# ASM001-design-1.net
KiCad netlist of a schematic drawn in Altium Designer
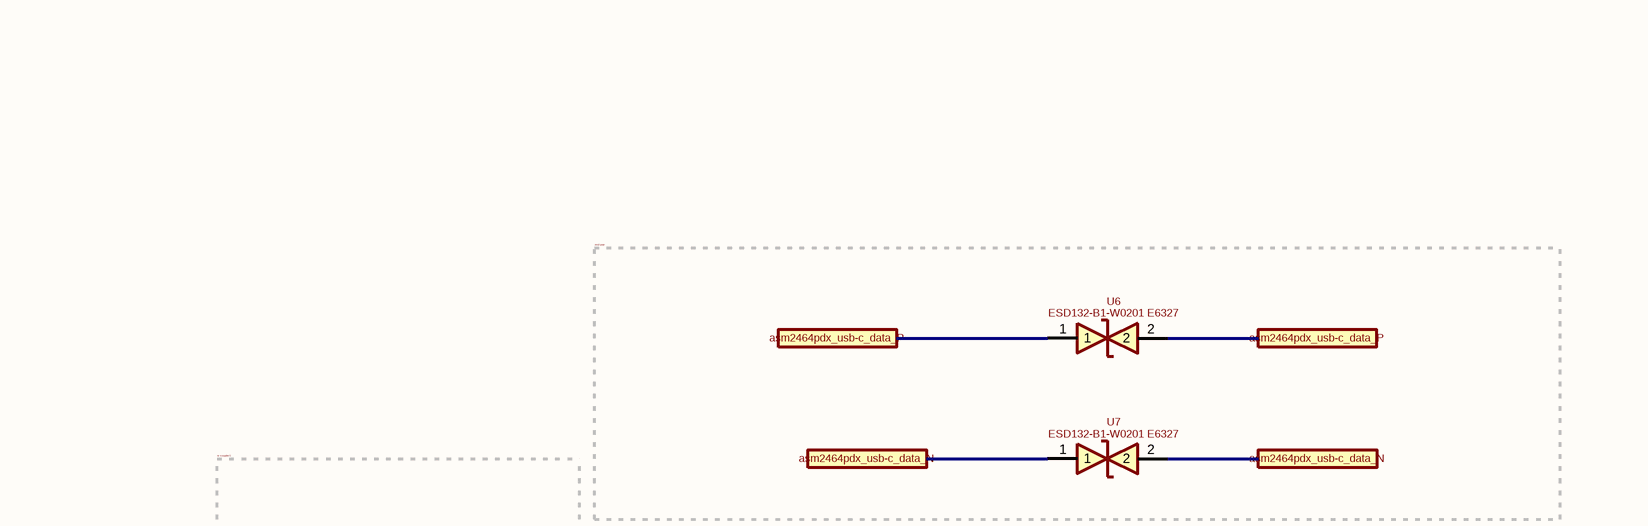
[diagram p0: ASM001-design-1.SchDoc, top column 2 of 4]
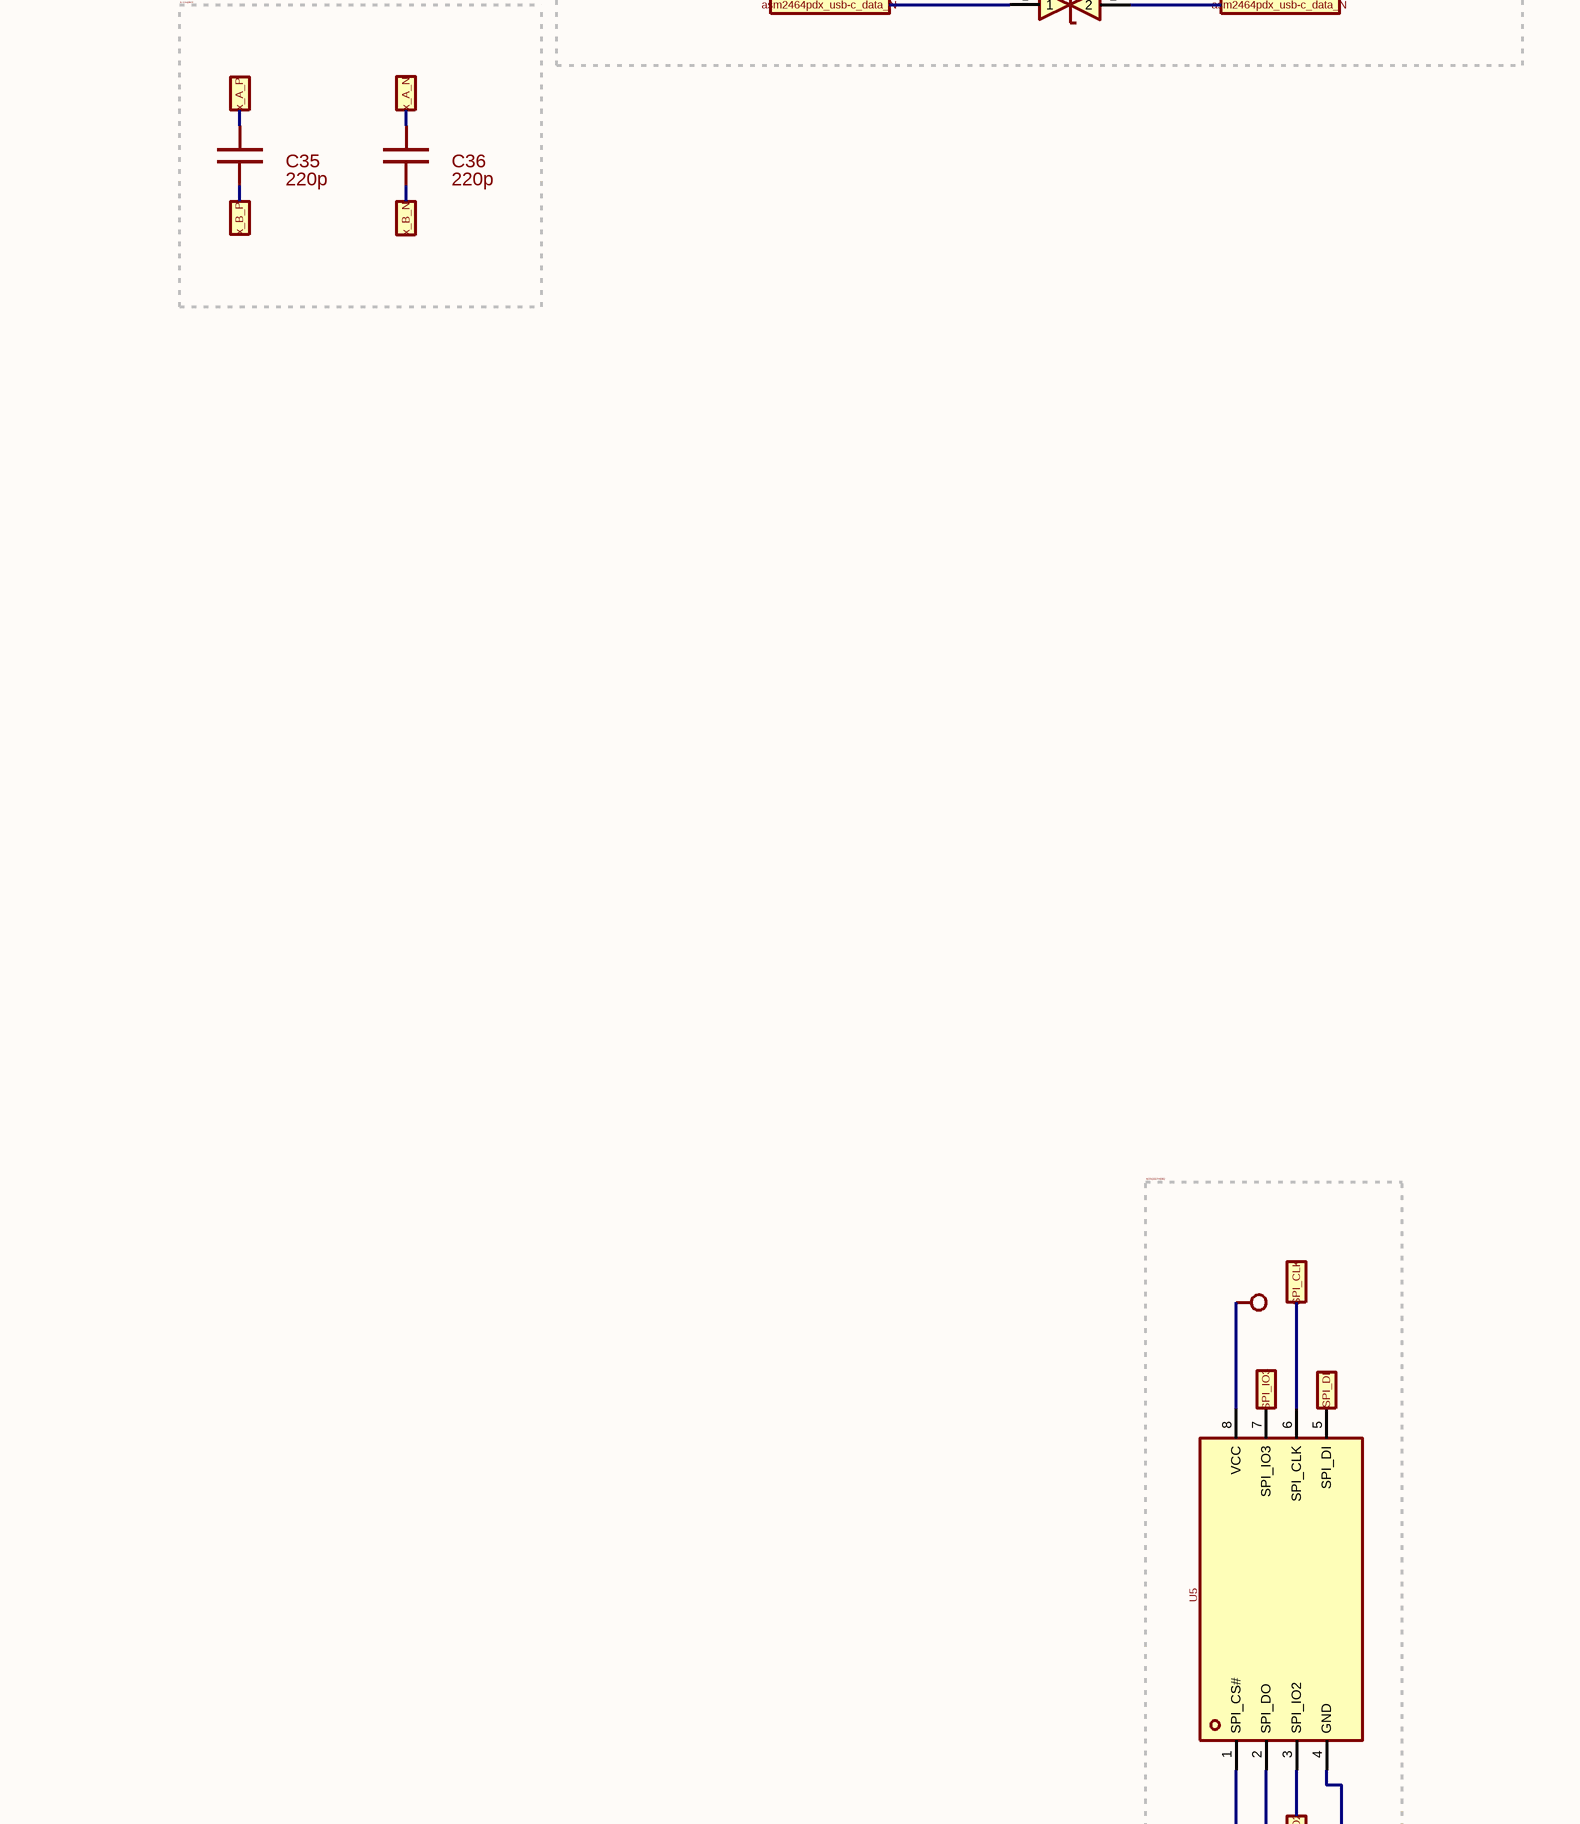
[diagram p1: ASM001-design-1.SchDoc, centre column 2 of 4]
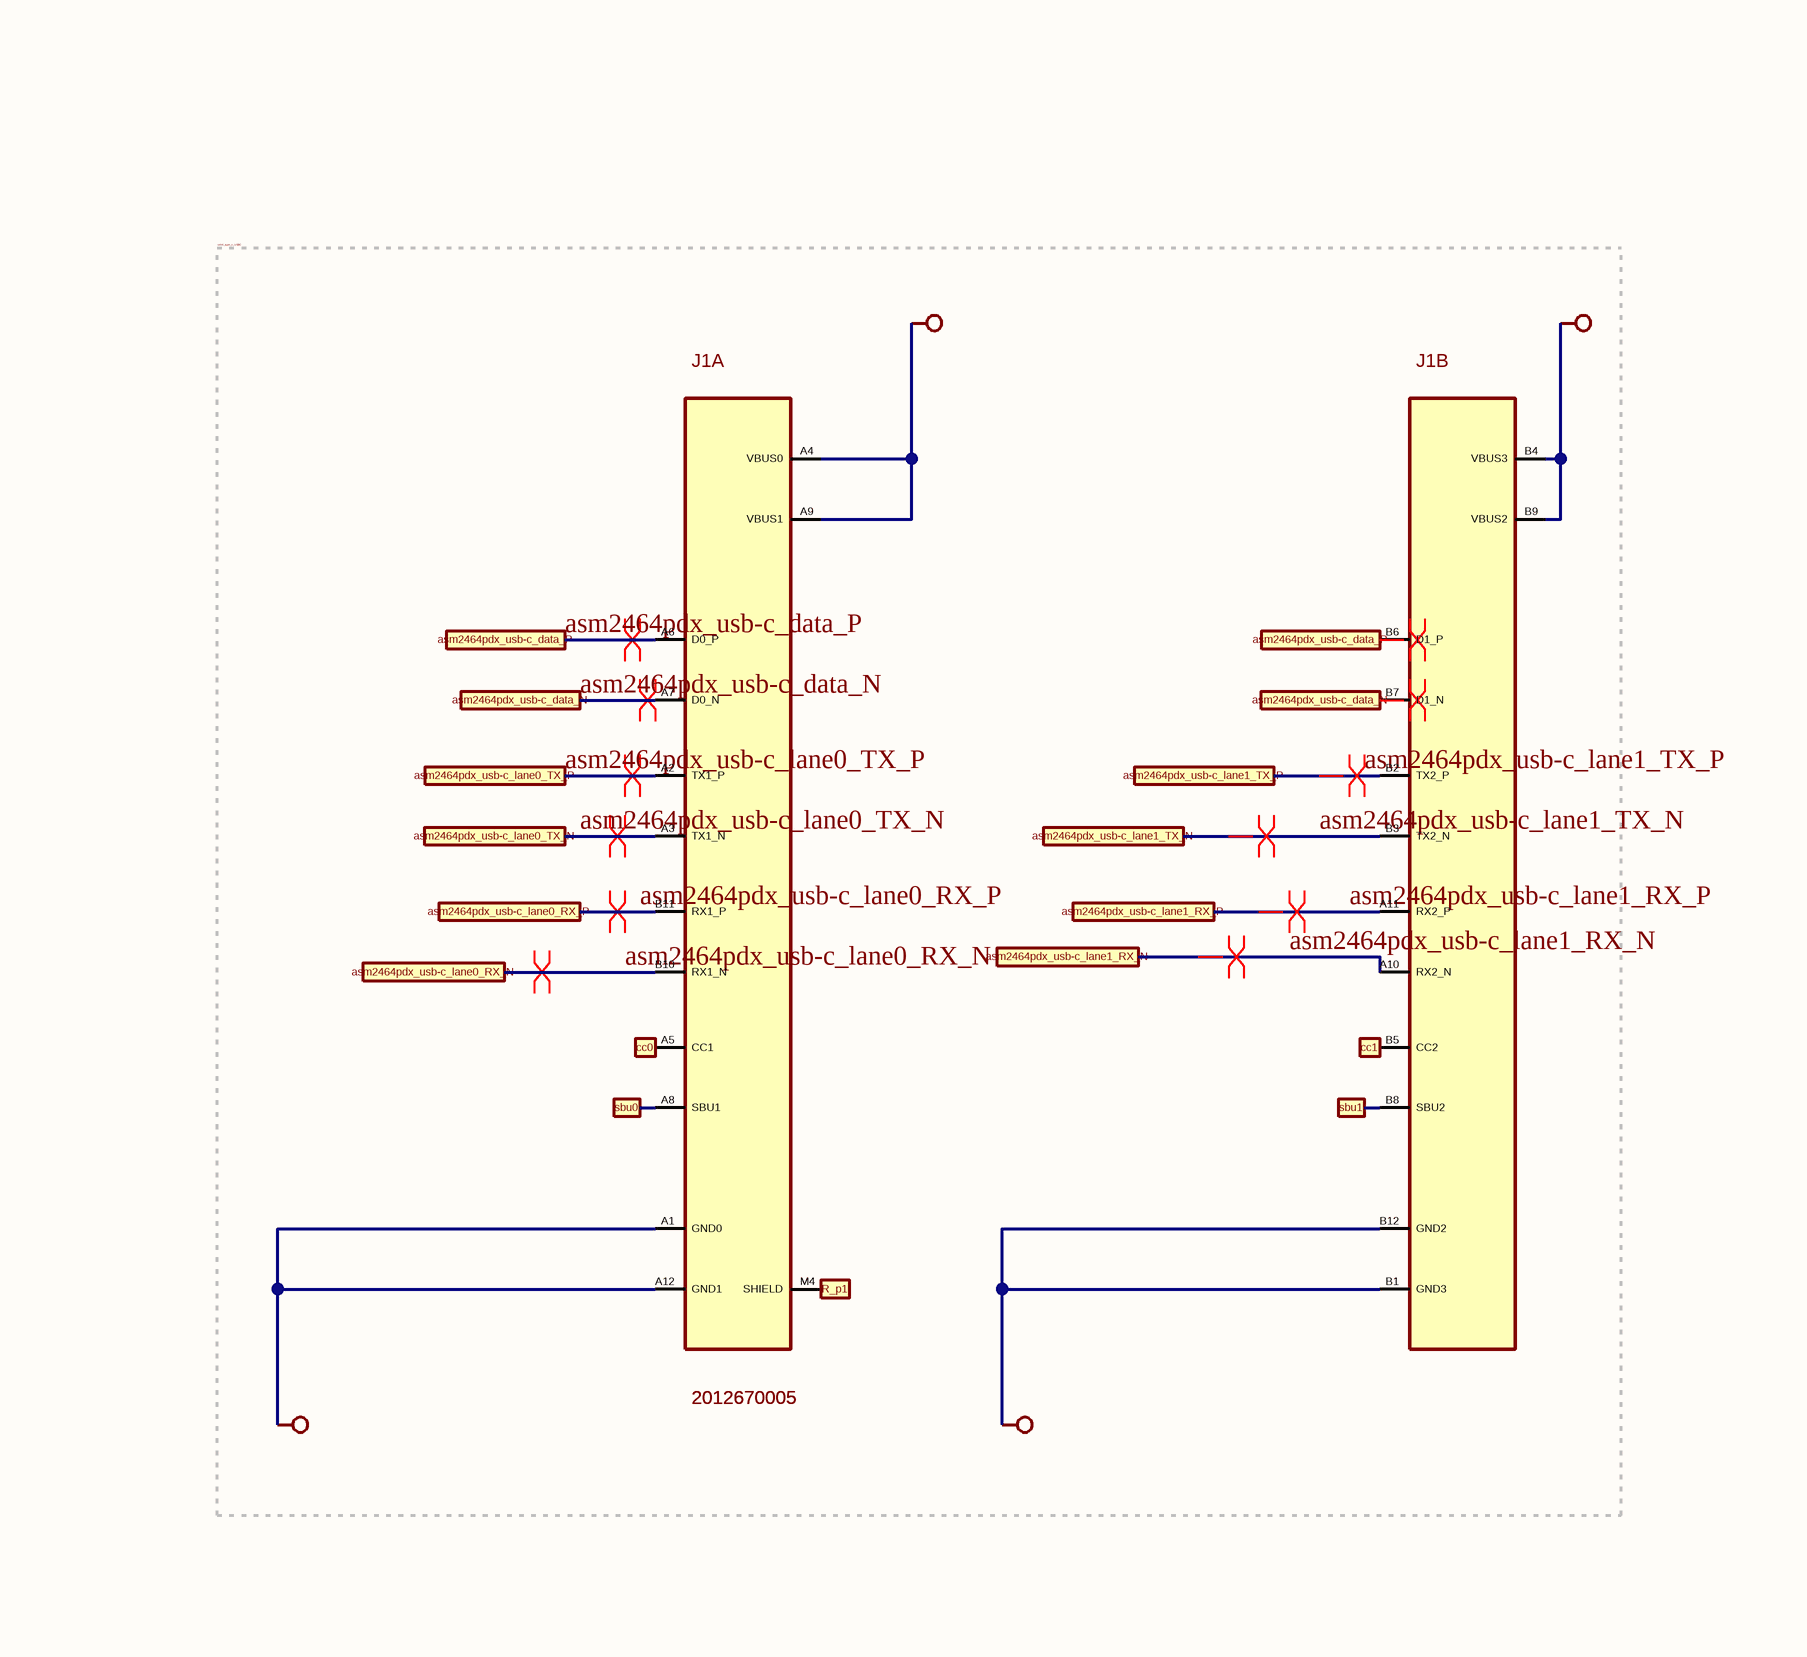
[diagram p2: ASM001-design-1.SchDoc, centre column 3 of 4]
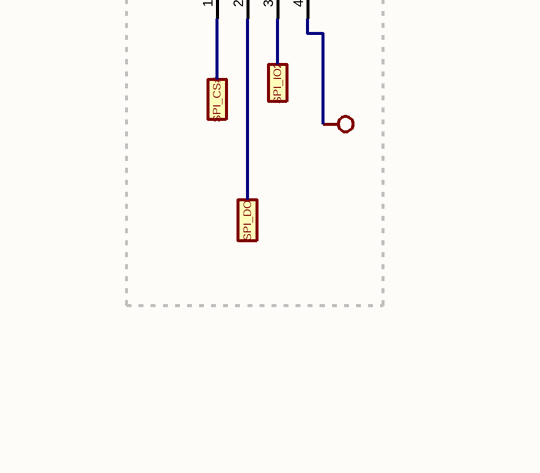
[diagram p3: ASM001-design-1.SchDoc, bottom column 2 of 4]
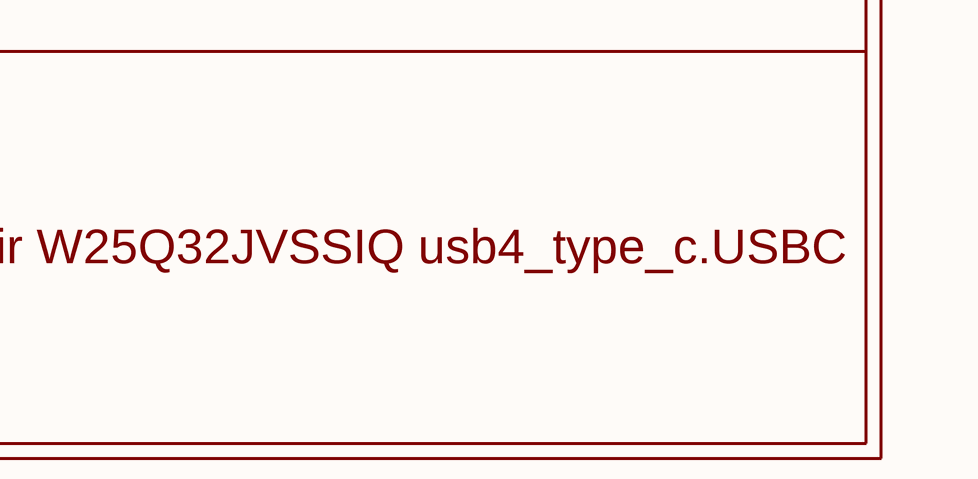
[diagram p4: ASM001-design-1.SchDoc, bottom column 4 of 4]

(export (version "E")
  (design (tool "Eeschema 10.0.6"))
  (components
    (comp (ref "C35")
      (value "220p")
      (footprint "SMT_0201$1")
      (description "block_cap")
      (fields (field (name "TOLERANCE") "0.2%") (field (name "MPN") "02013A1R5BAT2A"))
      (libsource (lib "ASM001-design") (part "block_cap"))
    )
    (comp (ref "C36")
      (value "220p")
      (footprint "SMT_0201$1")
      (description "block_cap")
      (fields (field (name "TOLERANCE") "0.2%") (field (name "MPN") "02013A1R5BAT2A"))
      (libsource (lib "ASM001-design") (part "block_cap"))
    )
    (comp (ref "J1")
      (value "2012670005")
      (footprint "USB_TYPE_C_CONNECTOR")
      (description "conn_component")
      (fields (field (name "ALTIUM_VALUE") "2012670005") (field (name "MANUFACTURER") "Molex"))
      (libsource (lib "ASM001-design") (part "conn_component"))
    )
    (comp (ref "U5")
      (value "W25Q32JVSSIQ")
      (footprint "LP$1")
      (description "C82344")
      (fields (field (name "MANUFACTURER") "Winbond"))
      (libsource (lib "ASM001-design") (part "C82344"))
    )
    (comp (ref "U6")
      (value "ESD132-B1-W0201 E6327")
      (footprint "LP$3")
      (description "C535164")
      (fields (field (name "MANUFACTURER") "Infineon"))
      (libsource (lib "ASM001-design") (part "C535164"))
    )
    (comp (ref "U7")
      (value "ESD132-B1-W0201 E6327")
      (footprint "LP$3")
      (description "C535164")
      (fields (field (name "MANUFACTURER") "Infineon"))
      (libsource (lib "ASM001-design") (part "C535164"))
    )
  )
  (nets
    (net (code "1") (name "/R_p1") (class "Default")
      (node (ref "J1") (pin "M4") (pinfunction "SHIELD_M4") (pintype "passive"))
    )
    (net (code "2") (name "/SPI_CLK") (class "Default")
      (node (ref "U5") (pin "6") (pinfunction "SPI_CLK_6") (pintype "passive"))
    )
    (net (code "3") (name "/SPI_CS#") (class "Default")
      (node (ref "U5") (pin "1") (pinfunction "SPI_CS#_1") (pintype "passive"))
    )
    (net (code "4") (name "/SPI_DI") (class "Default")
      (node (ref "U5") (pin "5") (pinfunction "SPI_DI_5") (pintype "passive"))
    )
    (net (code "5") (name "/SPI_DO") (class "Default")
      (node (ref "U5") (pin "2") (pinfunction "SPI_DO_2") (pintype "passive"))
    )
    (net (code "6") (name "/SPI_IO2") (class "Default")
      (node (ref "U5") (pin "3") (pinfunction "SPI_IO2_3") (pintype "passive"))
    )
    (net (code "7") (name "/SPI_IO3") (class "Default")
      (node (ref "U5") (pin "7") (pinfunction "SPI_IO3_7") (pintype "passive"))
    )
    (net (code "8") (name "/asm2464pdx_usb-c_data_N") (class "Default")
      (node (ref "J1") (pin "A7") (pinfunction "D0_N_A7") (pintype "passive"))
      (node (ref "J1") (pin "B7") (pinfunction "D1_N_B7") (pintype "passive"))
      (node (ref "U7") (pin "1") (pinfunction "1_1") (pintype "passive"))
      (node (ref "U7") (pin "2") (pinfunction "2_2") (pintype "passive"))
    )
    (net (code "9") (name "/asm2464pdx_usb-c_data_P") (class "Default")
      (node (ref "J1") (pin "A6") (pinfunction "D0_P_A6") (pintype "passive"))
      (node (ref "J1") (pin "B6") (pinfunction "D1_P_B6") (pintype "passive"))
      (node (ref "U6") (pin "1") (pinfunction "1_1") (pintype "passive"))
      (node (ref "U6") (pin "2") (pinfunction "2_2") (pintype "passive"))
    )
    (net (code "10") (name "/asm2464pdx_usb-c_lane0_RX_N") (class "Default")
      (node (ref "J1") (pin "B10") (pinfunction "RX1_N_B10") (pintype "passive"))
    )
    (net (code "11") (name "/asm2464pdx_usb-c_lane0_RX_P") (class "Default")
      (node (ref "J1") (pin "B11") (pinfunction "RX1_P_B11") (pintype "passive"))
    )
    (net (code "12") (name "/asm2464pdx_usb-c_lane0_TX_N") (class "Default")
      (node (ref "J1") (pin "A3") (pinfunction "TX1_N_A3") (pintype "passive"))
    )
    (net (code "13") (name "/asm2464pdx_usb-c_lane0_TX_P") (class "Default")
      (node (ref "J1") (pin "A2") (pinfunction "TX1_P_A2") (pintype "passive"))
    )
    (net (code "14") (name "/asm2464pdx_usb-c_lane1_RX_N") (class "Default")
      (node (ref "J1") (pin "A10") (pinfunction "RX2_N_A10") (pintype "passive"))
    )
    (net (code "15") (name "/asm2464pdx_usb-c_lane1_RX_P") (class "Default")
      (node (ref "J1") (pin "A11") (pinfunction "RX2_P_A11") (pintype "passive"))
    )
    (net (code "16") (name "/asm2464pdx_usb-c_lane1_TX_N") (class "Default")
      (node (ref "J1") (pin "B3") (pinfunction "TX2_N_B3") (pintype "passive"))
    )
    (net (code "17") (name "/asm2464pdx_usb-c_lane1_TX_P") (class "Default")
      (node (ref "J1") (pin "B2") (pinfunction "TX2_P_B2") (pintype "passive"))
    )
    (net (code "18") (name "/cc0") (class "Default")
      (node (ref "J1") (pin "A5") (pinfunction "CC1_A5") (pintype "passive"))
    )
    (net (code "19") (name "/cc1") (class "Default")
      (node (ref "J1") (pin "B5") (pinfunction "CC2_B5") (pintype "passive"))
    )
    (net (code "20") (name "/sbu0") (class "Default")
      (node (ref "J1") (pin "A8") (pinfunction "SBU1_A8") (pintype "passive"))
    )
    (net (code "21") (name "/sbu1") (class "Default")
      (node (ref "J1") (pin "B8") (pinfunction "SBU2_B8") (pintype "passive"))
    )
    (net (code "22") (name "/x_A_N") (class "Default")
      (node (ref "C36") (pin "1") (pinfunction "1_1") (pintype "passive"))
    )
    (net (code "23") (name "/x_A_P") (class "Default")
      (node (ref "C35") (pin "1") (pinfunction "1_1") (pintype "passive"))
    )
    (net (code "24") (name "/x_B_N") (class "Default")
      (node (ref "C36") (pin "2") (pinfunction "2_2") (pintype "passive"))
    )
    (net (code "25") (name "/x_B_P") (class "Default")
      (node (ref "C35") (pin "2") (pinfunction "2_2") (pintype "passive"))
    )
    (net (code "26") (name "<NO NET>") (class "Default")
      (node (ref "J1") (pin "A1") (pinfunction "GND0_A1") (pintype "passive"))
      (node (ref "J1") (pin "A12") (pinfunction "GND1_A12") (pintype "passive"))
      (node (ref "J1") (pin "A4") (pinfunction "VBUS0_A4") (pintype "passive"))
      (node (ref "J1") (pin "A9") (pinfunction "VBUS1_A9") (pintype "passive"))
      (node (ref "J1") (pin "B1") (pinfunction "GND3_B1") (pintype "passive"))
      (node (ref "J1") (pin "B12") (pinfunction "GND2_B12") (pintype "passive"))
      (node (ref "J1") (pin "B4") (pinfunction "VBUS3_B4") (pintype "passive"))
      (node (ref "J1") (pin "B9") (pinfunction "VBUS2_B9") (pintype "passive"))
      (node (ref "U5") (pin "4") (pinfunction "GND_4") (pintype "passive"))
      (node (ref "U5") (pin "8") (pinfunction "VCC_8") (pintype "passive"))
    )
  )
)
